# STM32G0_microcontroller.net
KiCad netlist of a schematic drawn in Altium Designer
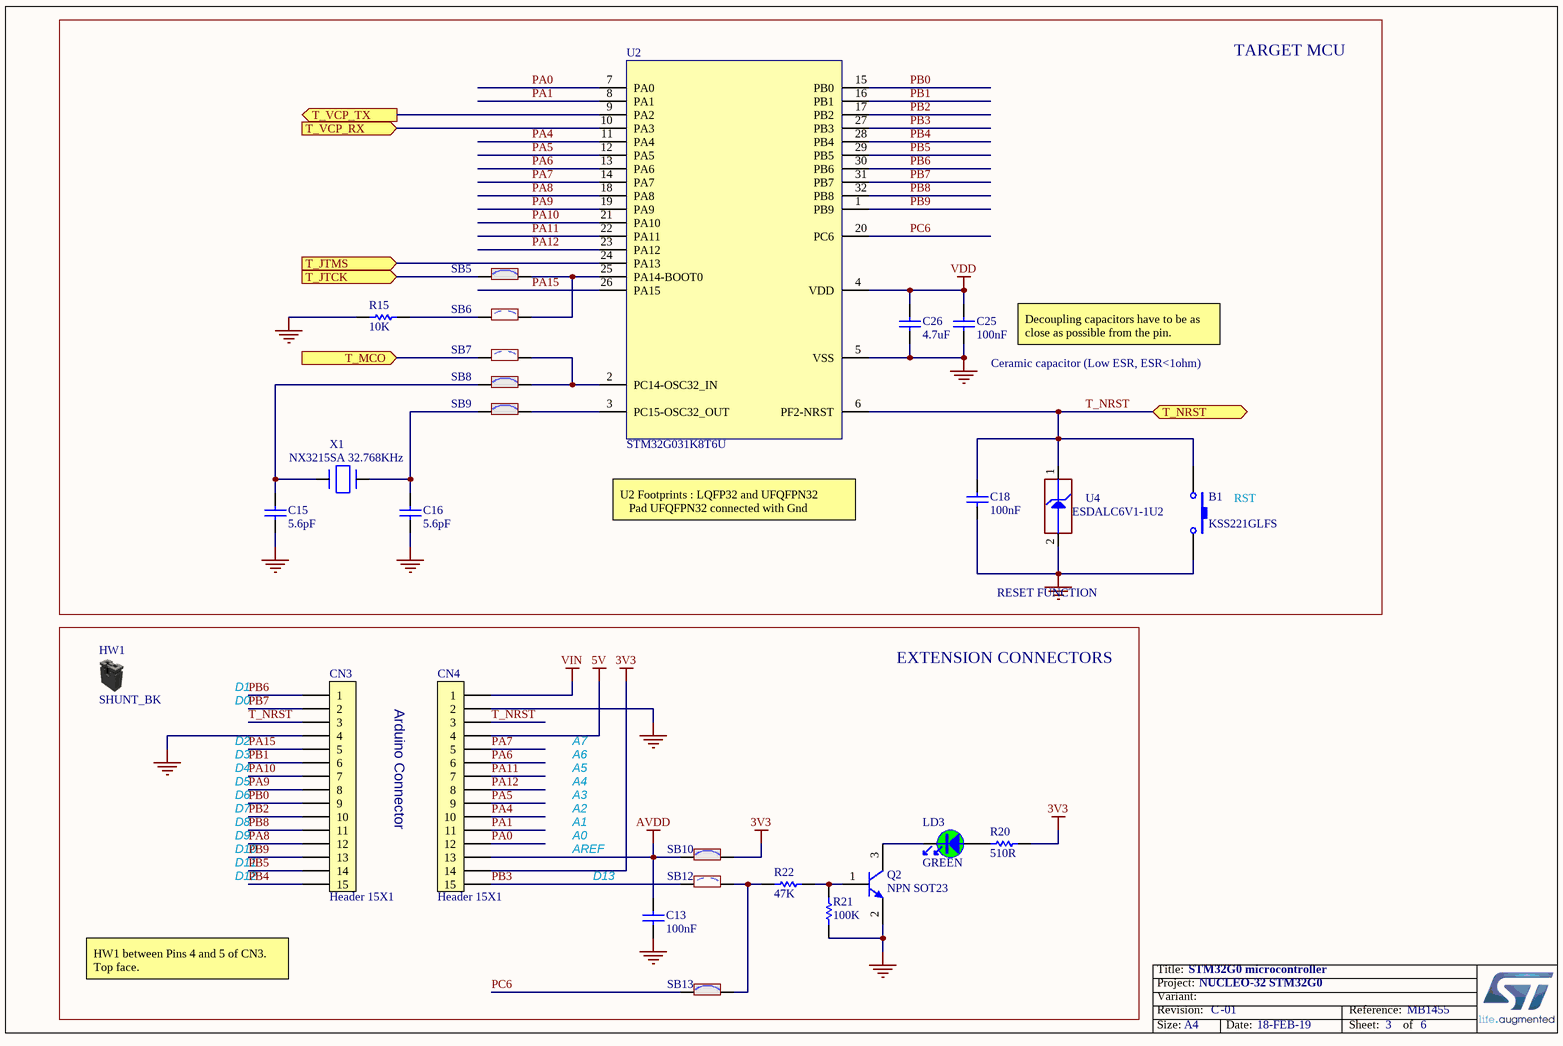
[diagram p0: STM32G0_microcontroller.SchDoc]

(export (version "E")
  (design (tool "Eeschema 10.0.6"))
  (components
    (comp (ref "B1")
      (value "KSS221GLFS")
      (footprint "SWI_C&K_ITT_KSS221G")
      (description "Subminiature Side Actuated Tact Switch for SMT - KSS series - 2.0 Newtons - Gull wing, SPST")
      (fields
        (field (name "INTERNAL_PART_NUMBER") "MCD-01335")
        (field (name "MANUFACTURER") "C&K")
        (field (name "PROVIDED_BY") "SUBCO")
      )
      (libsource (lib "MCD_PARTS_database") (part "SW-PB"))
    )
    (comp (ref "C13")
      (value "100nF")
      (footprint "C0402")
      (description "Capacitor, MLCC, 100nF, 16V, X7R, 10%, 0402, T=0,5mm")
      (fields
        (field (name "INTERNAL_PART_NUMBER") "MCD-00102")
        (field (name "MANUFACTURER_PART_NUMBER") "CC0402KRX7R7BB104")
        (field (name "PROVIDED_BY") "SUBCO")
      )
      (libsource (lib "MCD_PARTS_database") (part "Capacitor"))
    )
    (comp (ref "C15")
      (value "5.6pF")
      (footprint "C0402")
      (description "Capacitor, MLCC, 5.6pF, 50V, NPO, +/- 0.1pF, 0402, T=0,5mm")
      (fields
        (field (name "INTERNAL_PART_NUMBER") "MCD-01374")
        (field (name "MANUFACTURER_PART_NUMBER") "CC0402BRNPO9BN5R6")
        (field (name "PROVIDED_BY") "SUBCO")
      )
      (libsource (lib "MCD_PARTS_database") (part "Capacitor"))
    )
    (comp (ref "C16")
      (value "5.6pF")
      (footprint "C0402")
      (description "Capacitor, MLCC, 5.6pF, 50V, NPO, +/- 0.1pF, 0402, T=0,5mm")
      (fields
        (field (name "INTERNAL_PART_NUMBER") "MCD-01374")
        (field (name "MANUFACTURER_PART_NUMBER") "CC0402BRNPO9BN5R6")
        (field (name "PROVIDED_BY") "SUBCO")
      )
      (libsource (lib "MCD_PARTS_database") (part "Capacitor"))
    )
    (comp (ref "C18")
      (value "100nF")
      (footprint "C0402")
      (description "Capacitor, MLCC, 100nF, 16V, X7R, 10%, 0402, T=0,5mm")
      (fields
        (field (name "INTERNAL_PART_NUMBER") "MCD-00102")
        (field (name "MANUFACTURER_PART_NUMBER") "CC0402KRX7R7BB104")
        (field (name "PROVIDED_BY") "SUBCO")
      )
      (libsource (lib "MCD_PARTS_database") (part "Capacitor"))
    )
    (comp (ref "C25")
      (value "100nF")
      (footprint "C0402")
      (description "Capacitor, MLCC, 100nF, 16V, X7R, 10%, 0402, T=0,5mm")
      (fields
        (field (name "INTERNAL_PART_NUMBER") "MCD-00102")
        (field (name "MANUFACTURER_PART_NUMBER") "CC0402KRX7R7BB104")
        (field (name "PROVIDED_BY") "SUBCO")
      )
      (libsource (lib "MCD_PARTS_database") (part "Capacitor"))
    )
    (comp (ref "C26")
      (value "4.7uF")
      (footprint "C0402")
      (description "Capacitor, MLCC, 4.7uF, 6V3, X5R, 20%, 0402, T=0,5mm")
      (fields
        (field (name "INTERNAL_PART_NUMBER") "MCD-00096")
        (field (name "MANUFACTURER_PART_NUMBER") "GRM155R60J475ME87")
        (field (name "PROVIDED_BY") "SUBCO")
      )
      (libsource (lib "MCD_PARTS_database") (part "Capacitor"))
    )
    (comp (ref "CN3")
      (value "Header 15X1")
      (footprint "CON_LYCN_313115S161145")
      (description "Pin header, 15x1, 2,54mm, VR, TH, Height 6mm/6mm")
      (fields
        (field (name "INTERNAL_PART_NUMBER") "MCD-01332")
        (field (name "MANUFACTURER_PART_NUMBER") "313115S161145")
        (field (name "PROVIDED_BY") "SUBCO")
      )
      (libsource (lib "") (part "Header 15x1_1"))
    )
    (comp (ref "CN4")
      (value "Header 15X1")
      (footprint "CON_LYCN_313115S161145")
      (description "Pin header, 15x1, 2,54mm, VR, TH, Height 6mm/6mm")
      (fields
        (field (name "INTERNAL_PART_NUMBER") "MCD-01332")
        (field (name "MANUFACTURER_PART_NUMBER") "313115S161145")
        (field (name "PROVIDED_BY") "SUBCO")
      )
      (libsource (lib "MCD_PARTS_database") (part "Header 15x1"))
    )
    (comp (ref "HW1")
      (value "SHUNT_BK")
      (description "SHUNT, 2.54mm, height 6.10mm, BLACK")
      (fields
        (field (name "INTERNAL_PART_NUMBER") "MCD-00122")
        (field (name "MANUFACTURER_PART_NUMBER") "SNT-100-BK-G")
        (field (name "PROVIDED_BY") "SUBCO")
      )
      (libsource (lib "MCD_PARTS_database") (part "Shunt Black 2.54mm"))
    )
    (comp (ref "LD3")
      (value "GREEN")
      (footprint "LED_0603_GREEN")
      (description "LED, Green, 0603")
      (fields
        (field (name "INTERNAL_PART_NUMBER") "MCD-00050")
        (field (name "MANUFACTURER_PART_NUMBER") "19-213SYGC/S530-E2/TR8")
        (field (name "PROVIDED_BY") "SUBCO")
      )
      (libsource (lib "MCD_PARTS_database") (part "LED_green"))
    )
    (comp (ref "Q2")
      (value "NPN SOT23")
      (footprint "NPN_SOT23")
      (description "NPN Bipolar Transistor")
      (fields
        (field (name "INTERNAL_PART_NUMBER") "MCD-00073")
        (field (name "MANUFACTURER_PART_NUMBER") "BSR14")
        (field (name "PROVIDED_BY") "SUBCO")
      )
      (libsource (lib "MCD_PARTS_database") (part "9013-SOT23"))
    )
    (comp (ref "R15")
      (value "10K")
      (footprint "R0402")
      (description "Resistor,10K,0402,1%,1/16W")
      (fields
        (field (name "INTERNAL_PART_NUMBER") "MCD-00053")
        (field (name "MANUFACTURER_PART_NUMBER") "RC0402FR-0710KL")
        (field (name "PROVIDED_BY") "SUBCO")
      )
      (libsource (lib "MCD_PARTS_database") (part "Resistor"))
    )
    (comp (ref "R20")
      (value "510R")
      (footprint "R0402")
      (description "Resistor,510R,0402,1%,1/16W")
      (fields
        (field (name "INTERNAL_PART_NUMBER") "MCD-00064")
        (field (name "MANUFACTURER_PART_NUMBER") "RC0402FR-07510RL")
        (field (name "PROVIDED_BY") "SUBCO")
      )
      (libsource (lib "MCD_PARTS_database") (part "Resistor"))
    )
    (comp (ref "R21")
      (value "100K")
      (footprint "R0402")
      (description "Resistor,100K,0402,1%,1/16W")
      (fields
        (field (name "INTERNAL_PART_NUMBER") "MCD-00059")
        (field (name "MANUFACTURER_PART_NUMBER") "RC0402FR-07100KL")
        (field (name "PROVIDED_BY") "SUBCO")
      )
      (libsource (lib "MCD_PARTS_database") (part "Resistor"))
    )
    (comp (ref "R22")
      (value "47K")
      (footprint "R0402")
      (description "Resistor,47K,0402,1%,1/16W")
      (fields
        (field (name "INTERNAL_PART_NUMBER") "MCD-00063")
        (field (name "MANUFACTURER_PART_NUMBER") "RC0402FR-0747KL")
        (field (name "PROVIDED_BY") "SUBCO")
      )
      (libsource (lib "MCD_PARTS_database") (part "Resistor"))
    )
    (comp (ref "SB5")
      (value "SB_ON")
      (footprint "SOLDER-BRIDGE_R0603-0R")
      (description "Solder Bridge ON")
      (fields
        (field (name "INTERNAL_PART_NUMBER") "MCD-00071")
        (field (name "MANUFACTURER_PART_NUMBER") "RC0603JR-070RL")
        (field (name "PROVIDED_BY") "SUBCO")
      )
      (libsource (lib "MCD_PARTS_database") (part "SB_ON"))
    )
    (comp (ref "SB6")
      (value "SB_OFF")
      (footprint "SOLDER-BRIDGE_R0603-0R")
      (description "Solder Bridge OFF")
      (fields
        (field (name "INTERNAL_PART_NUMBER") "MCD-00072")
        (field (name "MANUFACTURER_PART_NUMBER") "RC0603JR-070RL")
        (field (name "PROVIDED_BY") "SUBCO")
      )
      (libsource (lib "MCD_PARTS_database") (part "SB_OFF"))
    )
    (comp (ref "SB7")
      (value "SB_OFF")
      (footprint "SOLDER-BRIDGE_R0603-0R")
      (description "Solder Bridge OFF")
      (fields
        (field (name "INTERNAL_PART_NUMBER") "MCD-00072")
        (field (name "MANUFACTURER_PART_NUMBER") "RC0603JR-070RL")
        (field (name "PROVIDED_BY") "SUBCO")
      )
      (libsource (lib "MCD_PARTS_database") (part "SB_OFF"))
    )
    (comp (ref "SB8")
      (value "SB_ON")
      (footprint "SOLDER-BRIDGE_R0603-0R")
      (description "Solder Bridge ON")
      (fields
        (field (name "INTERNAL_PART_NUMBER") "MCD-00071")
        (field (name "MANUFACTURER_PART_NUMBER") "RC0603JR-070RL")
        (field (name "PROVIDED_BY") "SUBCO")
      )
      (libsource (lib "MCD_PARTS_database") (part "SB_ON"))
    )
    (comp (ref "SB9")
      (value "SB_ON")
      (footprint "SOLDER-BRIDGE_R0603-0R")
      (description "Solder Bridge ON")
      (fields
        (field (name "INTERNAL_PART_NUMBER") "MCD-00071")
        (field (name "MANUFACTURER_PART_NUMBER") "RC0603JR-070RL")
        (field (name "PROVIDED_BY") "SUBCO")
      )
      (libsource (lib "MCD_PARTS_database") (part "SB_ON"))
    )
    (comp (ref "SB10")
      (value "SB_ON")
      (footprint "SOLDER-BRIDGE_R0603-0R")
      (description "Solder Bridge ON")
      (fields
        (field (name "INTERNAL_PART_NUMBER") "MCD-00071")
        (field (name "MANUFACTURER_PART_NUMBER") "RC0603JR-070RL")
        (field (name "PROVIDED_BY") "SUBCO")
      )
      (libsource (lib "MCD_PARTS_database") (part "SB_ON"))
    )
    (comp (ref "SB12")
      (value "SB_OFF")
      (footprint "SOLDER-BRIDGE_R0603-0R")
      (description "Solder Bridge OFF")
      (fields
        (field (name "INTERNAL_PART_NUMBER") "MCD-00072")
        (field (name "MANUFACTURER_PART_NUMBER") "RC0603JR-070RL")
        (field (name "PROVIDED_BY") "SUBCO")
      )
      (libsource (lib "MCD_PARTS_database") (part "SB_OFF"))
    )
    (comp (ref "SB13")
      (value "SB_ON")
      (footprint "SOLDER-BRIDGE_R0603-0R")
      (description "Solder Bridge ON")
      (fields
        (field (name "INTERNAL_PART_NUMBER") "MCD-00071")
        (field (name "MANUFACTURER_PART_NUMBER") "RC0603JR-070RL")
        (field (name "PROVIDED_BY") "SUBCO")
      )
      (libsource (lib "MCD_PARTS_database") (part "SB_ON"))
    )
    (comp (ref "U2")
      (value "STM32G031K8T6U")
      (footprint "ICC_LQFP32_7X7_P080__UFQFPN32-EPAD_5X5_P050__DI")
      (fields
        (field (name "MANUFACTURER") "STMICROELECTRONICS")
        (field (name "INTERNAL_PART_NUMBER") "MCD-01738")
        (field (name "PROVIDED_BY") "SUBCO with ST control")
      )
      (libsource (lib "MCD_PARTS_database") (part "STM32G031K8T6U"))
    )
    (comp (ref "U4")
      (value "ESDALC6V1-1U2")
      (footprint "ESD_ST0201")
      (description "ESD protection 6V1")
      (fields
        (field (name "INTERNAL_PART_NUMBER") "MCD-00170")
        (field (name "MANUFACTURER") "STMICROELECTRONICS")
        (field (name "PROVIDED_BY") "SUBCO with ST control")
      )
      (libsource (lib "MCD_PARTS_database") (part "ESD-TRANSIL"))
    )
    (comp (ref "X1")
      (value "NX3215SA 32.768KHz")
      (footprint "CRY_NX3215SA_2P")
      (description "Crystal 32.768kHz, 6pF, +-20ppm, 50Kohms max, SMD")
      (fields
        (field (name "INTERNAL_PART_NUMBER") "MCD-00091")
        (field (name "MANUFACTURER_PART_NUMBER") "NX3215SA 32.768KHz EXS00A-MU00525")
        (field (name "PROVIDED_BY") "SUBCO")
      )
      (libsource (lib "MCD_PARTS_database") (part "XTAL_2_PINS"))
    )
  )
  (nets
    (net (code "1") (name "/PA0") (class "Default")
      (node (ref "CN4") (pin "12") (pinfunction "12_12") (pintype "passive"))
      (node (ref "U2") (pin "7") (pinfunction "PA0_7") (pintype "passive"))
    )
    (net (code "2") (name "/PA1") (class "Default")
      (node (ref "CN4") (pin "11") (pinfunction "11_11") (pintype "passive"))
      (node (ref "U2") (pin "8") (pinfunction "PA1_8") (pintype "passive"))
    )
    (net (code "3") (name "/PA4") (class "Default")
      (node (ref "CN4") (pin "10") (pinfunction "10_10") (pintype "passive"))
      (node (ref "U2") (pin "11") (pinfunction "PA4_11") (pintype "passive"))
    )
    (net (code "4") (name "/PA5") (class "Default")
      (node (ref "CN4") (pin "9") (pinfunction "9_9") (pintype "passive"))
      (node (ref "U2") (pin "12") (pinfunction "PA5_12") (pintype "passive"))
    )
    (net (code "5") (name "/PA6") (class "Default")
      (node (ref "CN4") (pin "6") (pinfunction "6_6") (pintype "passive"))
      (node (ref "U2") (pin "13") (pinfunction "PA6_13") (pintype "passive"))
    )
    (net (code "6") (name "/PA7") (class "Default")
      (node (ref "CN4") (pin "5") (pinfunction "5_5") (pintype "passive"))
      (node (ref "U2") (pin "14") (pinfunction "PA7_14") (pintype "passive"))
    )
    (net (code "7") (name "/PA8") (class "Default")
      (node (ref "CN3") (pin "12") (pinfunction "12_12") (pintype "passive"))
      (node (ref "U2") (pin "18") (pinfunction "PA8_18") (pintype "passive"))
    )
    (net (code "8") (name "/PA9") (class "Default")
      (node (ref "CN3") (pin "8") (pinfunction "8_8") (pintype "passive"))
      (node (ref "U2") (pin "19") (pinfunction "PA9_19") (pintype "passive"))
    )
    (net (code "9") (name "/PA10") (class "Default")
      (node (ref "CN3") (pin "7") (pinfunction "7_7") (pintype "passive"))
      (node (ref "U2") (pin "21") (pinfunction "PA10_21") (pintype "passive"))
    )
    (net (code "10") (name "/PA11") (class "Default")
      (node (ref "CN4") (pin "7") (pinfunction "7_7") (pintype "passive"))
      (node (ref "U2") (pin "22") (pinfunction "PA11_22") (pintype "passive"))
    )
    (net (code "11") (name "/PA12") (class "Default")
      (node (ref "CN4") (pin "8") (pinfunction "8_8") (pintype "passive"))
      (node (ref "U2") (pin "23") (pinfunction "PA12_23") (pintype "passive"))
    )
    (net (code "12") (name "/PA15") (class "Default")
      (node (ref "CN3") (pin "5") (pinfunction "5_5") (pintype "passive"))
      (node (ref "U2") (pin "26") (pinfunction "PA15_26") (pintype "passive"))
    )
    (net (code "13") (name "/PB0") (class "Default")
      (node (ref "CN3") (pin "9") (pinfunction "9_9") (pintype "passive"))
      (node (ref "U2") (pin "15") (pinfunction "PB0_15") (pintype "passive"))
    )
    (net (code "14") (name "/PB1") (class "Default")
      (node (ref "CN3") (pin "6") (pinfunction "6_6") (pintype "passive"))
      (node (ref "U2") (pin "16") (pinfunction "PB1_16") (pintype "passive"))
    )
    (net (code "15") (name "/PB2") (class "Default")
      (node (ref "CN3") (pin "10") (pinfunction "10_10") (pintype "passive"))
      (node (ref "U2") (pin "17") (pinfunction "PB2_17") (pintype "passive"))
    )
    (net (code "16") (name "/PB3") (class "Default")
      (node (ref "CN4") (pin "15") (pinfunction "15_15") (pintype "passive"))
      (node (ref "SB12") (pin "1") (pinfunction "1_1") (pintype "passive"))
      (node (ref "U2") (pin "27") (pinfunction "PB3_27") (pintype "passive"))
    )
    (net (code "17") (name "/PB4") (class "Default")
      (node (ref "CN3") (pin "15") (pinfunction "15_15") (pintype "passive"))
      (node (ref "U2") (pin "28") (pinfunction "PB4_28") (pintype "passive"))
    )
    (net (code "18") (name "/PB5") (class "Default")
      (node (ref "CN3") (pin "14") (pinfunction "14_14") (pintype "passive"))
      (node (ref "U2") (pin "29") (pinfunction "PB5_29") (pintype "passive"))
    )
    (net (code "19") (name "/PB6") (class "Default")
      (node (ref "CN3") (pin "1") (pinfunction "1_1") (pintype "passive"))
      (node (ref "U2") (pin "30") (pinfunction "PB6_30") (pintype "passive"))
    )
    (net (code "20") (name "/PB7") (class "Default")
      (node (ref "CN3") (pin "2") (pinfunction "2_2") (pintype "passive"))
      (node (ref "U2") (pin "31") (pinfunction "PB7_31") (pintype "passive"))
    )
    (net (code "21") (name "/PB8") (class "Default")
      (node (ref "CN3") (pin "11") (pinfunction "11_11") (pintype "passive"))
      (node (ref "U2") (pin "32") (pinfunction "PB8_32") (pintype "passive"))
    )
    (net (code "22") (name "/PB9") (class "Default")
      (node (ref "CN3") (pin "13") (pinfunction "13_13") (pintype "passive"))
      (node (ref "U2") (pin "1") (pinfunction "PB9_1") (pintype "passive"))
    )
    (net (code "23") (name "/PC6") (class "Default")
      (node (ref "SB13") (pin "1") (pinfunction "1_1") (pintype "passive"))
      (node (ref "U2") (pin "20") (pinfunction "PC6_20") (pintype "passive"))
    )
    (net (code "24") (name "/T_JTCK") (class "Default")
      (node (ref "SB5") (pin "1") (pinfunction "1_1") (pintype "passive"))
    )
    (net (code "25") (name "/T_JTMS") (class "Default")
      (node (ref "U2") (pin "24") (pinfunction "PA13_24") (pintype "passive"))
    )
    (net (code "26") (name "/T_MCO") (class "Default")
      (node (ref "SB7") (pin "1") (pinfunction "1_1") (pintype "passive"))
    )
    (net (code "27") (name "/T_NRST") (class "Default")
      (node (ref "B1") (pin "1") (pinfunction "1_1") (pintype "passive"))
      (node (ref "C18") (pin "2") (pinfunction "2_2") (pintype "passive"))
      (node (ref "CN3") (pin "3") (pinfunction "3_3") (pintype "passive"))
      (node (ref "CN4") (pin "3") (pinfunction "3_3") (pintype "passive"))
      (node (ref "U2") (pin "6") (pinfunction "PF2-NRST_6") (pintype "passive"))
      (node (ref "U4") (pin "1") (pinfunction "IO1_1") (pintype "passive"))
    )
    (net (code "28") (name "/T_VCP_RX") (class "Default")
      (node (ref "U2") (pin "10") (pinfunction "PA3_10") (pintype "passive"))
    )
    (net (code "29") (name "/T_VCP_TX") (class "Default")
      (node (ref "U2") (pin "9") (pinfunction "PA2_9") (pintype "passive"))
    )
    (net (code "30") (name "3V3") (class "Default")
      (node (ref "CN4") (pin "14") (pinfunction "14_14") (pintype "passive"))
      (node (ref "R20") (pin "2") (pinfunction "2_2") (pintype "passive"))
      (node (ref "SB10") (pin "2") (pinfunction "2_2") (pintype "passive"))
    )
    (net (code "31") (name "5V") (class "Default")
      (node (ref "CN4") (pin "4") (pinfunction "4_4") (pintype "passive"))
    )
    (net (code "32") (name "AVDD") (class "Default")
      (node (ref "C13") (pin "2") (pinfunction "2_2") (pintype "passive"))
      (node (ref "CN4") (pin "13") (pinfunction "13_13") (pintype "passive"))
      (node (ref "SB10") (pin "1") (pinfunction "1_1") (pintype "passive"))
    )
    (net (code "33") (name "GND") (class "Default")
      (node (ref "B1") (pin "2") (pinfunction "2_2") (pintype "passive"))
      (node (ref "C13") (pin "1") (pinfunction "1_1") (pintype "passive"))
      (node (ref "C15") (pin "1") (pinfunction "1_1") (pintype "passive"))
      (node (ref "C16") (pin "1") (pinfunction "1_1") (pintype "passive"))
      (node (ref "C18") (pin "1") (pinfunction "1_1") (pintype "passive"))
      (node (ref "C25") (pin "1") (pinfunction "1_1") (pintype "passive"))
      (node (ref "C26") (pin "1") (pinfunction "1_1") (pintype "passive"))
      (node (ref "CN3") (pin "4") (pinfunction "4_4") (pintype "passive"))
      (node (ref "CN4") (pin "2") (pinfunction "2_2") (pintype "passive"))
      (node (ref "Q2") (pin "2") (pinfunction "E_2") (pintype "passive"))
      (node (ref "R15") (pin "1") (pinfunction "1_1") (pintype "passive"))
      (node (ref "R21") (pin "1") (pinfunction "1_1") (pintype "passive"))
      (node (ref "U2") (pin "5") (pinfunction "VSS_5") (pintype "passive"))
      (node (ref "U4") (pin "2") (pinfunction "GND_2") (pintype "passive"))
    )
    (net (code "34") (name "Net-(LD3-Pad1)") (class "Default")
      (node (ref "LD3") (pin "1") (pintype "passive"))
      (node (ref "R20") (pin "1") (pinfunction "1_1") (pintype "passive"))
    )
    (net (code "35") (name "Net-(Q2-B)") (class "Default")
      (node (ref "Q2") (pin "1") (pinfunction "B_1") (pintype "passive"))
      (node (ref "R21") (pin "2") (pinfunction "2_2") (pintype "passive"))
      (node (ref "R22") (pin "2") (pinfunction "2_2") (pintype "passive"))
    )
    (net (code "36") (name "Net-(Q2-C)") (class "Default")
      (node (ref "LD3") (pin "2") (pintype "passive"))
      (node (ref "Q2") (pin "3") (pinfunction "C_3") (pintype "passive"))
    )
    (net (code "37") (name "Net-(R15-Pad2)") (class "Default")
      (node (ref "R15") (pin "2") (pinfunction "2_2") (pintype "passive"))
      (node (ref "SB6") (pin "1") (pinfunction "1_1") (pintype "passive"))
    )
    (net (code "38") (name "Net-(R22-Pad1)") (class "Default")
      (node (ref "R22") (pin "1") (pinfunction "1_1") (pintype "passive"))
      (node (ref "SB12") (pin "2") (pinfunction "2_2") (pintype "passive"))
      (node (ref "SB13") (pin "2") (pinfunction "2_2") (pintype "passive"))
    )
    (net (code "39") (name "Net-(U2-PA14-BOOT0)") (class "Default")
      (node (ref "SB5") (pin "2") (pinfunction "2_2") (pintype "passive"))
      (node (ref "SB6") (pin "2") (pinfunction "2_2") (pintype "passive"))
      (node (ref "U2") (pin "25") (pinfunction "PA14-BOOT0_25") (pintype "passive"))
    )
    (net (code "40") (name "Net-(U2-PC14-OSC32_IN)") (class "Default")
      (node (ref "SB7") (pin "2") (pinfunction "2_2") (pintype "passive"))
      (node (ref "SB8") (pin "2") (pinfunction "2_2") (pintype "passive"))
      (node (ref "U2") (pin "2") (pinfunction "PC14-OSC32_IN_2") (pintype "passive"))
    )
    (net (code "41") (name "Net-(U2-PC15-OSC32_OUT)") (class "Default")
      (node (ref "SB9") (pin "2") (pinfunction "2_2") (pintype "passive"))
      (node (ref "U2") (pin "3") (pinfunction "PC15-OSC32_OUT_3") (pintype "passive"))
    )
    (net (code "42") (name "Net-(X1-X1)") (class "Default")
      (node (ref "C15") (pin "2") (pinfunction "2_2") (pintype "passive"))
      (node (ref "SB8") (pin "1") (pinfunction "1_1") (pintype "passive"))
      (node (ref "X1") (pin "1") (pinfunction "X1_1") (pintype "passive"))
    )
    (net (code "43") (name "Net-(X1-X2)") (class "Default")
      (node (ref "C16") (pin "2") (pinfunction "2_2") (pintype "passive"))
      (node (ref "SB9") (pin "1") (pinfunction "1_1") (pintype "passive"))
      (node (ref "X1") (pin "2") (pinfunction "X2_2") (pintype "passive"))
    )
    (net (code "44") (name "VDD") (class "Default")
      (node (ref "C25") (pin "2") (pinfunction "2_2") (pintype "passive"))
      (node (ref "C26") (pin "2") (pinfunction "2_2") (pintype "passive"))
      (node (ref "U2") (pin "4") (pinfunction "VDD_4") (pintype "passive"))
    )
    (net (code "45") (name "VIN") (class "Default")
      (node (ref "CN4") (pin "1") (pinfunction "1_1") (pintype "passive"))
    )
  )
)
